# pressuresense.net
KiCad netlist of a schematic drawn in EAGLE
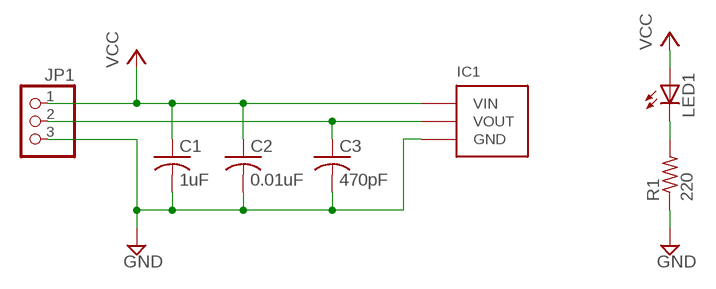
[diagram p0: schematic, sheet 1]

(export (version "E")
  (design (tool "Eeschema 10.0.6"))
  (components
    (comp (ref "C1")
      (value "1uF")
      (footprint "eagle-import:C0805K")
      (libsource (lib "eagle-import") (part "C-USC0805K"))
    )
    (comp (ref "C2")
      (value "0.01uF")
      (footprint "eagle-import:C0805K")
      (libsource (lib "eagle-import") (part "C-USC0805K"))
    )
    (comp (ref "C3")
      (value "470pF")
      (footprint "eagle-import:C0805K")
      (libsource (lib "eagle-import") (part "C-USC0805K"))
    )
    (comp (ref "IC1")
      (value "MPXA4250AC6U")
      (footprint "eagle-import:MPXA4250AC6U")
      (libsource (lib "eagle-import") (part "MPXA4250AC6U"))
    )
    (comp (ref "JP1")
      (value "PINHD-1X3")
      (footprint "eagle-import:1X03")
      (libsource (lib "eagle-import") (part "PINHD-1X3"))
    )
    (comp (ref "LED1")
      (value "LEDCHIP-LED0805")
      (footprint "eagle-import:CHIP-LED0805")
      (libsource (lib "eagle-import") (part "LEDCHIP-LED0805"))
    )
    (comp (ref "R1")
      (value "220")
      (footprint "eagle-import:R0805")
      (libsource (lib "eagle-import") (part "R-US_R0805"))
    )
  )
  (nets
    (net (code "1") (name "GND") (class "Default")
      (node (ref "C1") (pin "2") (pinfunction "2_2") (pintype "passive"))
      (node (ref "C2") (pin "2") (pinfunction "2_2") (pintype "passive"))
      (node (ref "C3") (pin "2") (pinfunction "2_2") (pintype "passive"))
      (node (ref "IC1") (pin "P$3") (pinfunction "GND_P$3") (pintype "bidirectional"))
      (node (ref "JP1") (pin "3") (pinfunction "3_3") (pintype "passive"))
      (node (ref "R1") (pin "1") (pinfunction "1_1") (pintype "passive"))
    )
    (net (code "2") (name "Net-(IC1-VOUT)") (class "Default")
      (node (ref "C3") (pin "1") (pinfunction "1_1") (pintype "passive"))
      (node (ref "IC1") (pin "P$4") (pinfunction "VOUT_P$4") (pintype "bidirectional"))
      (node (ref "JP1") (pin "2") (pinfunction "2_2") (pintype "passive"))
    )
    (net (code "3") (name "Net-(LED1-PadC)") (class "Default")
      (node (ref "LED1") (pin "C") (pinfunction "C_C") (pintype "passive"))
      (node (ref "R1") (pin "2") (pinfunction "2_2") (pintype "passive"))
    )
    (net (code "4") (name "VCC") (class "Default")
      (node (ref "C1") (pin "1") (pinfunction "1_1") (pintype "passive"))
      (node (ref "C2") (pin "1") (pinfunction "1_1") (pintype "passive"))
      (node (ref "IC1") (pin "P$2") (pinfunction "VIN_P$2") (pintype "bidirectional"))
      (node (ref "JP1") (pin "1") (pinfunction "1_1") (pintype "passive"))
      (node (ref "LED1") (pin "A") (pinfunction "A_A") (pintype "passive"))
    )
  )
)
